# Drivers.net
KiCad netlist of a schematic drawn in Altium Designer
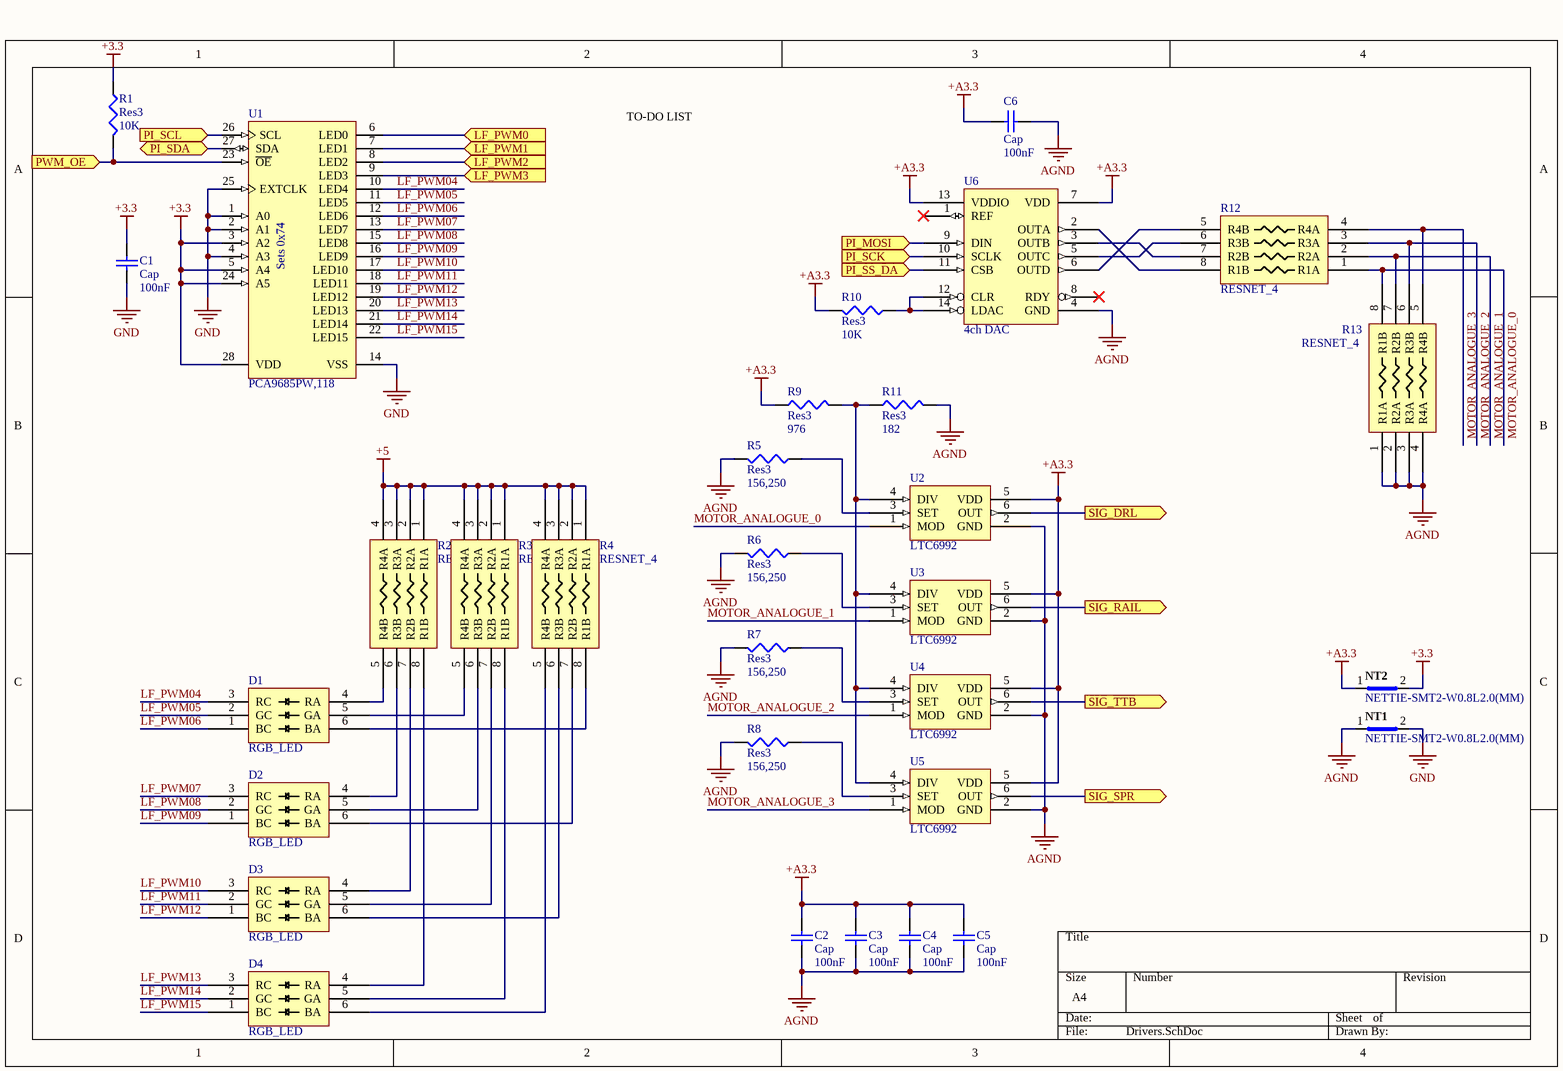
[diagram p0: Drivers.SchDoc]

(export (version "E")
  (design (tool "Eeschema 10.0.6"))
  (components
    (comp (ref "C1")
      (value "Cap")
      (footprint "C0805")
      (description "Capacitor")
      (fields (field (name "ALTIUM_VALUE") "100nF") (field (name "PUBLISHER") "Altium Limited"))
      (libsource (lib "Miscellaneous Devices") (part "Cap"))
    )
    (comp (ref "C2")
      (value "Cap")
      (footprint "C0805")
      (description "Capacitor")
      (fields (field (name "ALTIUM_VALUE") "100nF") (field (name "PUBLISHER") "Altium Limited"))
      (libsource (lib "Miscellaneous Devices") (part "Cap"))
    )
    (comp (ref "C3")
      (value "Cap")
      (footprint "C0805")
      (description "Capacitor")
      (fields (field (name "ALTIUM_VALUE") "100nF") (field (name "PUBLISHER") "Altium Limited"))
      (libsource (lib "Miscellaneous Devices") (part "Cap"))
    )
    (comp (ref "C4")
      (value "Cap")
      (footprint "C0805")
      (description "Capacitor")
      (fields (field (name "ALTIUM_VALUE") "100nF") (field (name "PUBLISHER") "Altium Limited"))
      (libsource (lib "Miscellaneous Devices") (part "Cap"))
    )
    (comp (ref "C5")
      (value "Cap")
      (footprint "C0805")
      (description "Capacitor")
      (fields (field (name "ALTIUM_VALUE") "100nF") (field (name "PUBLISHER") "Altium Limited"))
      (libsource (lib "Miscellaneous Devices") (part "Cap"))
    )
    (comp (ref "C6")
      (value "Cap")
      (footprint "C0805")
      (description "Capacitor")
      (fields (field (name "ALTIUM_VALUE") "100nF") (field (name "PUBLISHER") "Altium Limited"))
      (libsource (lib "Miscellaneous Devices") (part "Cap"))
    )
    (comp (ref "D1")
      (value "RGB_LED")
      (footprint "SLV6A-FKB")
      (description "RGB LED")
      (libsource (lib "ScienceSymbols") (part "RGB_LED"))
    )
    (comp (ref "D2")
      (value "RGB_LED")
      (footprint "SLV6A-FKB")
      (description "RGB LED")
      (libsource (lib "ScienceSymbols") (part "RGB_LED"))
    )
    (comp (ref "D3")
      (value "RGB_LED")
      (footprint "SLV6A-FKB")
      (description "RGB LED")
      (libsource (lib "ScienceSymbols") (part "RGB_LED"))
    )
    (comp (ref "D4")
      (value "RGB_LED")
      (footprint "SLV6A-FKB")
      (description "RGB LED")
      (libsource (lib "ScienceSymbols") (part "RGB_LED"))
    )
    (comp (ref "NT1")
      (value "NETTIE-SMT2-W0.8L2.0(MM)")
      (footprint "NETTIE-SMT2-W0.8L2.0(MM)")
      (description "Net-Tie, Surface Mount, 2.0 mm x 0.8 mm, 2 Pads (1.2 mm x 0.8 mm)")
      (fields (field (name "MANUFACTURER") "No Vendor"))
      (libsource (lib "Altium Content Vault") (part "NETTIE-2"))
    )
    (comp (ref "NT2")
      (value "NETTIE-SMT2-W0.8L2.0(MM)")
      (footprint "NETTIE-SMT2-W0.8L2.0(MM)")
      (description "Net-Tie, Surface Mount, 2.0 mm x 0.8 mm, 2 Pads (1.2 mm x 0.8 mm)")
      (fields (field (name "MANUFACTURER") "No Vendor"))
      (libsource (lib "Altium Content Vault") (part "NETTIE-2"))
    )
    (comp (ref "R1")
      (value "Res3")
      (footprint "C0805")
      (description "Resistor")
      (fields (field (name "ALTIUM_VALUE") "10K") (field (name "PUBLISHER") "Altium Limited"))
      (libsource (lib "Miscellaneous Devices") (part "Res3"))
    )
    (comp (ref "R2")
      (value "RESNET_4")
      (footprint "744C083")
      (description "4-Resistor Network")
      (libsource (lib "ScienceSymbols") (part "RESNET_4"))
    )
    (comp (ref "R3")
      (value "RESNET_4")
      (footprint "744C083")
      (description "4-Resistor Network")
      (libsource (lib "ScienceSymbols") (part "RESNET_4"))
    )
    (comp (ref "R4")
      (value "RESNET_4")
      (footprint "744C083")
      (description "4-Resistor Network")
      (libsource (lib "ScienceSymbols") (part "RESNET_4"))
    )
    (comp (ref "R5")
      (value "Res3")
      (footprint "C0805")
      (description "Resistor")
      (fields (field (name "ALTIUM_VALUE") "156,250") (field (name "PUBLISHER") "Altium Limited"))
      (libsource (lib "Miscellaneous Devices") (part "Res3"))
    )
    (comp (ref "R6")
      (value "Res3")
      (footprint "C0805")
      (description "Resistor")
      (fields (field (name "ALTIUM_VALUE") "156,250") (field (name "PUBLISHER") "Altium Limited"))
      (libsource (lib "Miscellaneous Devices") (part "Res3"))
    )
    (comp (ref "R7")
      (value "Res3")
      (footprint "C0805")
      (description "Resistor")
      (fields (field (name "ALTIUM_VALUE") "156,250") (field (name "PUBLISHER") "Altium Limited"))
      (libsource (lib "Miscellaneous Devices") (part "Res3"))
    )
    (comp (ref "R8")
      (value "Res3")
      (footprint "C0805")
      (description "Resistor")
      (fields (field (name "ALTIUM_VALUE") "156,250") (field (name "PUBLISHER") "Altium Limited"))
      (libsource (lib "Miscellaneous Devices") (part "Res3"))
    )
    (comp (ref "R9")
      (value "Res3")
      (footprint "C0805")
      (description "Resistor")
      (fields (field (name "ALTIUM_VALUE") "976") (field (name "PUBLISHER") "Altium Limited"))
      (libsource (lib "Miscellaneous Devices") (part "Res3"))
    )
    (comp (ref "R10")
      (value "Res3")
      (footprint "C0805")
      (description "Resistor")
      (fields (field (name "ALTIUM_VALUE") "10K") (field (name "PUBLISHER") "Altium Limited"))
      (libsource (lib "Miscellaneous Devices") (part "Res3"))
    )
    (comp (ref "R11")
      (value "Res3")
      (footprint "C0805")
      (description "Resistor")
      (fields (field (name "ALTIUM_VALUE") "182") (field (name "PUBLISHER") "Altium Limited"))
      (libsource (lib "Miscellaneous Devices") (part "Res3"))
    )
    (comp (ref "R12")
      (value "RESNET_4")
      (footprint "CAY16F4")
      (description "4-Resistor Network")
      (libsource (lib "") (part "RESNET_4_1"))
    )
    (comp (ref "R13")
      (value "RESNET_4")
      (footprint "CAY16F4")
      (description "4-Resistor Network")
      (libsource (lib "") (part "RESNET_4_2"))
    )
    (comp (ref "U1")
      (value "PCA9685PW,118")
      (footprint "SOT361-1_V")
      (fields (field (name "PARTNUMBER") "PCA9685"))
      (libsource (lib "Altium Content Vault") (part "NXP-PCA9685-SOT361-1"))
    )
    (comp (ref "U2")
      (value "LTC6992")
      (footprint "LTC6992")
      (description "Voltage-Controlled Pulse \r\nWidth Modulator (PWM)")
      (libsource (lib "ScienceSymbols") (part "LTC6992"))
    )
    (comp (ref "U3")
      (value "LTC6992")
      (footprint "LTC6992")
      (description "Voltage-Controlled Pulse \r\nWidth Modulator (PWM)")
      (libsource (lib "ScienceSymbols") (part "LTC6992"))
    )
    (comp (ref "U4")
      (value "LTC6992")
      (footprint "LTC6992")
      (description "Voltage-Controlled Pulse \r\nWidth Modulator (PWM)")
      (libsource (lib "ScienceSymbols") (part "LTC6992"))
    )
    (comp (ref "U5")
      (value "LTC6992")
      (footprint "LTC6992")
      (description "Voltage-Controlled Pulse \r\nWidth Modulator (PWM)")
      (libsource (lib "ScienceSymbols") (part "LTC6992"))
    )
    (comp (ref "U6")
      (value "4ch DAC")
      (footprint "MAX5715")
      (libsource (lib "ScienceSymbols") (part "MAX5715"))
    )
  )
  (nets
    (net (code "1") (name "+3.3") (class "Default")
      (node (ref "C1") (pin "2") (pinfunction "2_2") (pintype "passive"))
      (node (ref "NT2") (pin "2") (pinfunction "Net2_2") (pintype "passive"))
      (node (ref "R1") (pin "1") (pinfunction "1_1") (pintype "passive"))
      (node (ref "U1") (pin "24") (pinfunction "A5_24") (pintype "input"))
      (node (ref "U1") (pin "28") (pinfunction "VDD_28") (pintype "power_in"))
      (node (ref "U1") (pin "3") (pinfunction "A2_3") (pintype "input"))
      (node (ref "U1") (pin "5") (pinfunction "A4_5") (pintype "input"))
    )
    (net (code "2") (name "+5") (class "Default")
      (node (ref "R2") (pin "1") (pinfunction "R1A_1") (pintype "passive"))
      (node (ref "R2") (pin "2") (pinfunction "R2A_2") (pintype "passive"))
      (node (ref "R2") (pin "3") (pinfunction "R3A_3") (pintype "passive"))
      (node (ref "R2") (pin "4") (pinfunction "R4A_4") (pintype "passive"))
      (node (ref "R3") (pin "1") (pinfunction "R1A_1") (pintype "passive"))
      (node (ref "R3") (pin "2") (pinfunction "R2A_2") (pintype "passive"))
      (node (ref "R3") (pin "3") (pinfunction "R3A_3") (pintype "passive"))
      (node (ref "R3") (pin "4") (pinfunction "R4A_4") (pintype "passive"))
      (node (ref "R4") (pin "1") (pinfunction "R1A_1") (pintype "passive"))
      (node (ref "R4") (pin "2") (pinfunction "R2A_2") (pintype "passive"))
      (node (ref "R4") (pin "3") (pinfunction "R3A_3") (pintype "passive"))
      (node (ref "R4") (pin "4") (pinfunction "R4A_4") (pintype "passive"))
    )
    (net (code "3") (name "+A3.3") (class "Default")
      (node (ref "C2") (pin "2") (pinfunction "2_2") (pintype "passive"))
      (node (ref "C3") (pin "2") (pinfunction "2_2") (pintype "passive"))
      (node (ref "C4") (pin "2") (pinfunction "2_2") (pintype "passive"))
      (node (ref "C5") (pin "2") (pinfunction "2_2") (pintype "passive"))
      (node (ref "C6") (pin "2") (pinfunction "2_2") (pintype "passive"))
      (node (ref "NT2") (pin "1") (pinfunction "Net1_1") (pintype "passive"))
      (node (ref "R10") (pin "2") (pinfunction "2_2") (pintype "passive"))
      (node (ref "R9") (pin "1") (pinfunction "1_1") (pintype "passive"))
      (node (ref "U2") (pin "5") (pinfunction "VDD_5") (pintype "power_in"))
      (node (ref "U3") (pin "5") (pinfunction "VDD_5") (pintype "power_in"))
      (node (ref "U4") (pin "5") (pinfunction "VDD_5") (pintype "power_in"))
      (node (ref "U5") (pin "5") (pinfunction "VDD_5") (pintype "power_in"))
      (node (ref "U6") (pin "13") (pinfunction "VDDIO_13") (pintype "power_in"))
      (node (ref "U6") (pin "7") (pinfunction "VDD_7") (pintype "power_in"))
    )
    (net (code "4") (name "/LF_PWM0") (class "Default")
      (node (ref "U1") (pin "6") (pinfunction "LED0_6") (pintype "tri_state"))
    )
    (net (code "5") (name "/LF_PWM1") (class "Default")
      (node (ref "U1") (pin "7") (pinfunction "LED1_7") (pintype "tri_state"))
    )
    (net (code "6") (name "/LF_PWM2") (class "Default")
      (node (ref "U1") (pin "8") (pinfunction "LED2_8") (pintype "tri_state"))
    )
    (net (code "7") (name "/LF_PWM3") (class "Default")
      (node (ref "U1") (pin "9") (pinfunction "LED3_9") (pintype "tri_state"))
    )
    (net (code "8") (name "/LF_PWM04") (class "Default")
      (node (ref "D1") (pin "3") (pinfunction "RC_3") (pintype "passive"))
      (node (ref "U1") (pin "10") (pinfunction "LED4_10") (pintype "tri_state"))
    )
    (net (code "9") (name "/LF_PWM05") (class "Default")
      (node (ref "D1") (pin "2") (pinfunction "GC_2") (pintype "passive"))
      (node (ref "U1") (pin "11") (pinfunction "LED5_11") (pintype "tri_state"))
    )
    (net (code "10") (name "/LF_PWM06") (class "Default")
      (node (ref "D1") (pin "1") (pinfunction "BC_1") (pintype "passive"))
      (node (ref "U1") (pin "12") (pinfunction "LED6_12") (pintype "tri_state"))
    )
    (net (code "11") (name "/LF_PWM07") (class "Default")
      (node (ref "D2") (pin "3") (pinfunction "RC_3") (pintype "passive"))
      (node (ref "U1") (pin "13") (pinfunction "LED7_13") (pintype "tri_state"))
    )
    (net (code "12") (name "/LF_PWM08") (class "Default")
      (node (ref "D2") (pin "2") (pinfunction "GC_2") (pintype "passive"))
      (node (ref "U1") (pin "15") (pinfunction "LED8_15") (pintype "tri_state"))
    )
    (net (code "13") (name "/LF_PWM09") (class "Default")
      (node (ref "D2") (pin "1") (pinfunction "BC_1") (pintype "passive"))
      (node (ref "U1") (pin "16") (pinfunction "LED9_16") (pintype "tri_state"))
    )
    (net (code "14") (name "/LF_PWM10") (class "Default")
      (node (ref "D3") (pin "3") (pinfunction "RC_3") (pintype "passive"))
      (node (ref "U1") (pin "17") (pinfunction "LED10_17") (pintype "tri_state"))
    )
    (net (code "15") (name "/LF_PWM11") (class "Default")
      (node (ref "D3") (pin "2") (pinfunction "GC_2") (pintype "passive"))
      (node (ref "U1") (pin "18") (pinfunction "LED11_18") (pintype "tri_state"))
    )
    (net (code "16") (name "/LF_PWM12") (class "Default")
      (node (ref "D3") (pin "1") (pinfunction "BC_1") (pintype "passive"))
      (node (ref "U1") (pin "19") (pinfunction "LED12_19") (pintype "tri_state"))
    )
    (net (code "17") (name "/LF_PWM13") (class "Default")
      (node (ref "D4") (pin "3") (pinfunction "RC_3") (pintype "passive"))
      (node (ref "U1") (pin "20") (pinfunction "LED13_20") (pintype "tri_state"))
    )
    (net (code "18") (name "/LF_PWM14") (class "Default")
      (node (ref "D4") (pin "2") (pinfunction "GC_2") (pintype "passive"))
      (node (ref "U1") (pin "21") (pinfunction "LED14_21") (pintype "tri_state"))
    )
    (net (code "19") (name "/LF_PWM15") (class "Default")
      (node (ref "D4") (pin "1") (pinfunction "BC_1") (pintype "passive"))
      (node (ref "U1") (pin "22") (pinfunction "LED15_22") (pintype "tri_state"))
    )
    (net (code "20") (name "/MOTOR_ANALOGUE_0") (class "Default")
      (node (ref "R12") (pin "1") (pinfunction "R1A_1") (pintype "passive"))
      (node (ref "R13") (pin "8") (pinfunction "R1B_8") (pintype "passive"))
      (node (ref "U2") (pin "1") (pinfunction "MOD_1") (pintype "input"))
    )
    (net (code "21") (name "/MOTOR_ANALOGUE_1") (class "Default")
      (node (ref "R12") (pin "2") (pinfunction "R2A_2") (pintype "passive"))
      (node (ref "R13") (pin "7") (pinfunction "R2B_7") (pintype "passive"))
      (node (ref "U3") (pin "1") (pinfunction "MOD_1") (pintype "input"))
    )
    (net (code "22") (name "/MOTOR_ANALOGUE_2") (class "Default")
      (node (ref "R12") (pin "3") (pinfunction "R3A_3") (pintype "passive"))
      (node (ref "R13") (pin "6") (pinfunction "R3B_6") (pintype "passive"))
      (node (ref "U4") (pin "1") (pinfunction "MOD_1") (pintype "input"))
    )
    (net (code "23") (name "/MOTOR_ANALOGUE_3") (class "Default")
      (node (ref "R12") (pin "4") (pinfunction "R4A_4") (pintype "passive"))
      (node (ref "R13") (pin "5") (pinfunction "R4B_5") (pintype "passive"))
      (node (ref "U5") (pin "1") (pinfunction "MOD_1") (pintype "input"))
    )
    (net (code "24") (name "/PI_MOSI") (class "Default")
      (node (ref "U6") (pin "9") (pinfunction "DIN_9") (pintype "input"))
    )
    (net (code "25") (name "/PI_SCK") (class "Default")
      (node (ref "U6") (pin "10") (pinfunction "SCLK_10") (pintype "input"))
    )
    (net (code "26") (name "/PI_SCL") (class "Default")
      (node (ref "U1") (pin "26") (pinfunction "SCL_26") (pintype "input"))
    )
    (net (code "27") (name "/PI_SDA") (class "Default")
      (node (ref "U1") (pin "27") (pinfunction "SDA_27") (pintype "bidirectional"))
    )
    (net (code "28") (name "/PI_SS_DA") (class "Default")
      (node (ref "U6") (pin "11") (pinfunction "CSB_11") (pintype "input"))
    )
    (net (code "29") (name "/PWM_OE") (class "Default")
      (node (ref "R1") (pin "2") (pinfunction "2_2") (pintype "passive"))
      (node (ref "U1") (pin "23") (pinfunction "~{OE}_23") (pintype "input"))
    )
    (net (code "30") (name "/SIG_DRL") (class "Default")
      (node (ref "U2") (pin "6") (pinfunction "OUT_6") (pintype "output"))
    )
    (net (code "31") (name "/SIG_RAIL") (class "Default")
      (node (ref "U3") (pin "6") (pinfunction "OUT_6") (pintype "output"))
    )
    (net (code "32") (name "/SIG_SPR") (class "Default")
      (node (ref "U5") (pin "6") (pinfunction "OUT_6") (pintype "output"))
    )
    (net (code "33") (name "/SIG_TTB") (class "Default")
      (node (ref "U4") (pin "6") (pinfunction "OUT_6") (pintype "output"))
    )
    (net (code "34") (name "AGND") (class "Default")
      (node (ref "C2") (pin "1") (pinfunction "1_1") (pintype "passive"))
      (node (ref "C3") (pin "1") (pinfunction "1_1") (pintype "passive"))
      (node (ref "C4") (pin "1") (pinfunction "1_1") (pintype "passive"))
      (node (ref "C5") (pin "1") (pinfunction "1_1") (pintype "passive"))
      (node (ref "C6") (pin "1") (pinfunction "1_1") (pintype "passive"))
      (node (ref "NT1") (pin "1") (pinfunction "Net1_1") (pintype "passive"))
      (node (ref "R11") (pin "2") (pinfunction "2_2") (pintype "passive"))
      (node (ref "R13") (pin "1") (pinfunction "R1A_1") (pintype "passive"))
      (node (ref "R13") (pin "2") (pinfunction "R2A_2") (pintype "passive"))
      (node (ref "R13") (pin "3") (pinfunction "R3A_3") (pintype "passive"))
      (node (ref "R13") (pin "4") (pinfunction "R4A_4") (pintype "passive"))
      (node (ref "R5") (pin "2") (pinfunction "2_2") (pintype "passive"))
      (node (ref "R6") (pin "2") (pinfunction "2_2") (pintype "passive"))
      (node (ref "R7") (pin "2") (pinfunction "2_2") (pintype "passive"))
      (node (ref "R8") (pin "2") (pinfunction "2_2") (pintype "passive"))
      (node (ref "U2") (pin "2") (pinfunction "GND_2") (pintype "power_in"))
      (node (ref "U3") (pin "2") (pinfunction "GND_2") (pintype "power_in"))
      (node (ref "U4") (pin "2") (pinfunction "GND_2") (pintype "power_in"))
      (node (ref "U5") (pin "2") (pinfunction "GND_2") (pintype "power_in"))
      (node (ref "U6") (pin "4") (pinfunction "GND_4") (pintype "power_in"))
    )
    (net (code "35") (name "GND") (class "Default")
      (node (ref "C1") (pin "1") (pinfunction "1_1") (pintype "passive"))
      (node (ref "NT1") (pin "2") (pinfunction "Net2_2") (pintype "passive"))
      (node (ref "U1") (pin "1") (pinfunction "A0_1") (pintype "input"))
      (node (ref "U1") (pin "14") (pinfunction "VSS_14") (pintype "power_in"))
      (node (ref "U1") (pin "2") (pinfunction "A1_2") (pintype "input"))
      (node (ref "U1") (pin "25") (pinfunction "EXTCLK_25") (pintype "input"))
      (node (ref "U1") (pin "4") (pinfunction "A3_4") (pintype "input"))
    )
    (net (code "36") (name "Net-(D1-BA)") (class "Default")
      (node (ref "D1") (pin "6") (pinfunction "BA_6") (pintype "passive"))
      (node (ref "R4") (pin "8") (pinfunction "R1B_8") (pintype "passive"))
    )
    (net (code "37") (name "Net-(D1-GA)") (class "Default")
      (node (ref "D1") (pin "5") (pinfunction "GA_5") (pintype "passive"))
      (node (ref "R3") (pin "5") (pinfunction "R4B_5") (pintype "passive"))
    )
    (net (code "38") (name "Net-(D1-RA)") (class "Default")
      (node (ref "D1") (pin "4") (pinfunction "RA_4") (pintype "passive"))
      (node (ref "R2") (pin "5") (pinfunction "R4B_5") (pintype "passive"))
    )
    (net (code "39") (name "Net-(D2-BA)") (class "Default")
      (node (ref "D2") (pin "6") (pinfunction "BA_6") (pintype "passive"))
      (node (ref "R4") (pin "7") (pinfunction "R2B_7") (pintype "passive"))
    )
    (net (code "40") (name "Net-(D2-GA)") (class "Default")
      (node (ref "D2") (pin "5") (pinfunction "GA_5") (pintype "passive"))
      (node (ref "R3") (pin "6") (pinfunction "R3B_6") (pintype "passive"))
    )
    (net (code "41") (name "Net-(D2-RA)") (class "Default")
      (node (ref "D2") (pin "4") (pinfunction "RA_4") (pintype "passive"))
      (node (ref "R2") (pin "6") (pinfunction "R3B_6") (pintype "passive"))
    )
    (net (code "42") (name "Net-(D3-BA)") (class "Default")
      (node (ref "D3") (pin "6") (pinfunction "BA_6") (pintype "passive"))
      (node (ref "R4") (pin "6") (pinfunction "R3B_6") (pintype "passive"))
    )
    (net (code "43") (name "Net-(D3-GA)") (class "Default")
      (node (ref "D3") (pin "5") (pinfunction "GA_5") (pintype "passive"))
      (node (ref "R3") (pin "7") (pinfunction "R2B_7") (pintype "passive"))
    )
    (net (code "44") (name "Net-(D3-RA)") (class "Default")
      (node (ref "D3") (pin "4") (pinfunction "RA_4") (pintype "passive"))
      (node (ref "R2") (pin "7") (pinfunction "R2B_7") (pintype "passive"))
    )
    (net (code "45") (name "Net-(D4-BA)") (class "Default")
      (node (ref "D4") (pin "6") (pinfunction "BA_6") (pintype "passive"))
      (node (ref "R4") (pin "5") (pinfunction "R4B_5") (pintype "passive"))
    )
    (net (code "46") (name "Net-(D4-GA)") (class "Default")
      (node (ref "D4") (pin "5") (pinfunction "GA_5") (pintype "passive"))
      (node (ref "R3") (pin "8") (pinfunction "R1B_8") (pintype "passive"))
    )
    (net (code "47") (name "Net-(D4-RA)") (class "Default")
      (node (ref "D4") (pin "4") (pinfunction "RA_4") (pintype "passive"))
      (node (ref "R2") (pin "8") (pinfunction "R1B_8") (pintype "passive"))
    )
    (net (code "48") (name "Net-(R12-R1B)") (class "Default")
      (node (ref "R12") (pin "8") (pinfunction "R1B_8") (pintype "passive"))
      (node (ref "U6") (pin "2") (pinfunction "OUTA_2") (pintype "output"))
    )
    (net (code "49") (name "Net-(R12-R2B)") (class "Default")
      (node (ref "R12") (pin "7") (pinfunction "R2B_7") (pintype "passive"))
      (node (ref "U6") (pin "3") (pinfunction "OUTB_3") (pintype "output"))
    )
    (net (code "50") (name "Net-(R12-R3B)") (class "Default")
      (node (ref "R12") (pin "6") (pinfunction "R3B_6") (pintype "passive"))
      (node (ref "U6") (pin "5") (pinfunction "OUTC_5") (pintype "output"))
    )
    (net (code "51") (name "Net-(R12-R4B)") (class "Default")
      (node (ref "R12") (pin "5") (pinfunction "R4B_5") (pintype "passive"))
      (node (ref "U6") (pin "6") (pinfunction "OUTD_6") (pintype "output"))
    )
    (net (code "52") (name "Net-(U2-DIV)") (class "Default")
      (node (ref "R11") (pin "1") (pinfunction "1_1") (pintype "passive"))
      (node (ref "R9") (pin "2") (pinfunction "2_2") (pintype "passive"))
      (node (ref "U2") (pin "4") (pinfunction "DIV_4") (pintype "input"))
      (node (ref "U3") (pin "4") (pinfunction "DIV_4") (pintype "input"))
      (node (ref "U4") (pin "4") (pinfunction "DIV_4") (pintype "input"))
      (node (ref "U5") (pin "4") (pinfunction "DIV_4") (pintype "input"))
    )
    (net (code "53") (name "Net-(U2-SET)") (class "Default")
      (node (ref "R5") (pin "1") (pinfunction "1_1") (pintype "passive"))
      (node (ref "U2") (pin "3") (pinfunction "SET_3") (pintype "input"))
    )
    (net (code "54") (name "Net-(U3-SET)") (class "Default")
      (node (ref "R6") (pin "1") (pinfunction "1_1") (pintype "passive"))
      (node (ref "U3") (pin "3") (pinfunction "SET_3") (pintype "input"))
    )
    (net (code "55") (name "Net-(U4-SET)") (class "Default")
      (node (ref "R7") (pin "1") (pinfunction "1_1") (pintype "passive"))
      (node (ref "U4") (pin "3") (pinfunction "SET_3") (pintype "input"))
    )
    (net (code "56") (name "Net-(U5-SET)") (class "Default")
      (node (ref "R8") (pin "1") (pinfunction "1_1") (pintype "passive"))
      (node (ref "U5") (pin "3") (pinfunction "SET_3") (pintype "input"))
    )
    (net (code "57") (name "Net-(U6-CLR)") (class "Default")
      (node (ref "R10") (pin "1") (pinfunction "1_1") (pintype "passive"))
      (node (ref "U6") (pin "12") (pinfunction "CLR_12") (pintype "input"))
      (node (ref "U6") (pin "14") (pinfunction "LDAC_14") (pintype "input"))
    )
    (net (code "58") (name "unconnected-(U6-RDY-Pad8)") (class "Default")
      (node (ref "U6") (pin "8") (pinfunction "RDY_8") (pintype "output+no_connect"))
    )
    (net (code "59") (name "unconnected-(U6-REF-Pad1)") (class "Default")
      (node (ref "U6") (pin "1") (pinfunction "REF_1") (pintype "bidirectional+no_connect"))
    )
  )
)
